# 4_cyber60-mxhs_power.net
KiCad netlist of a schematic drawn in Altium Designer
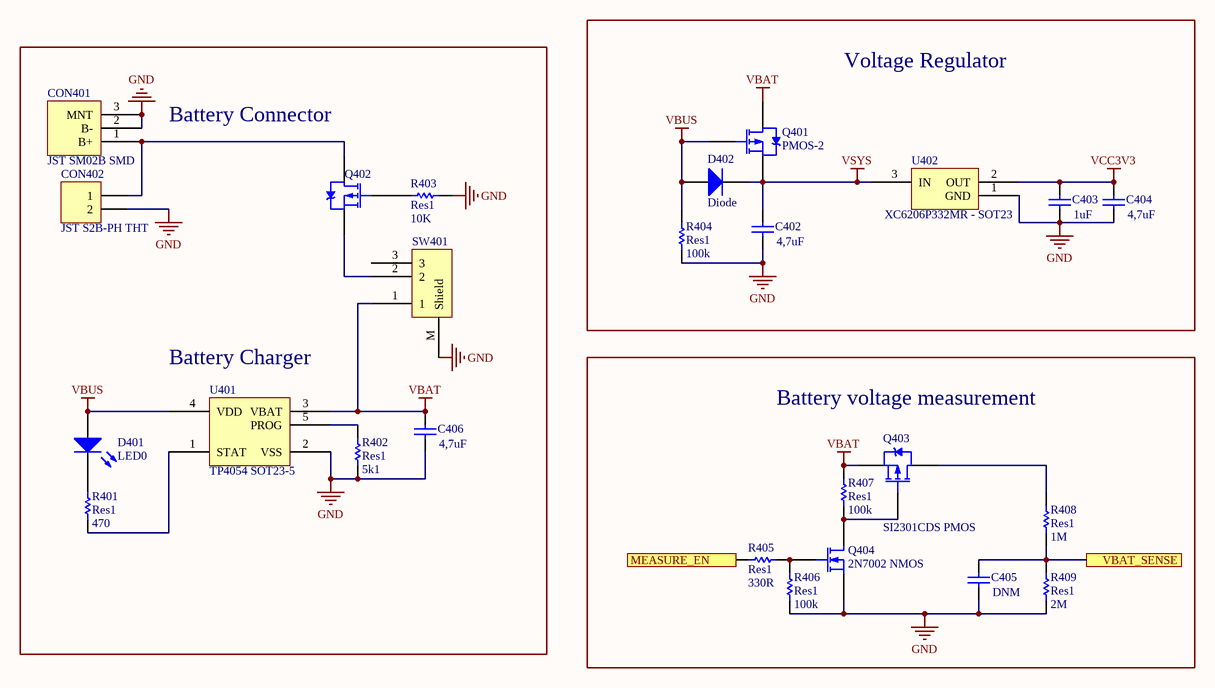
[diagram p0: 4_cyber60-mxhs_power.SchDoc]

(export (version "E")
  (design (tool "Eeschema 10.0.6"))
  (components
    (comp (ref "C402")
      (value "4,7uF")
      (footprint "C0603[1608]")
      (description "Capacitor")
      (fields (field (name "LCSC PART #") "C19666") (field (name "MRF.PART") "CL10A475KO8NNNC"))
      (libsource (lib "Miscellaneous Devices") (part "Cap"))
    )
    (comp (ref "C403")
      (value "1uF")
      (footprint "C0603[1608]")
      (description "Capacitor")
      (fields (field (name "MFG") "KEMET") (field (name "LCSC PART #") "C15849"))
      (libsource (lib "Miscellaneous Devices") (part "Cap"))
    )
    (comp (ref "C404")
      (value "4,7uF")
      (footprint "C0603[1608]")
      (description "Capacitor")
      (fields (field (name "LCSC PART #") "C19666") (field (name "MRF.PART") "CL10A475KO8NNNC"))
      (libsource (lib "Miscellaneous Devices") (part "Cap"))
    )
    (comp (ref "C405")
      (value "DNM")
      (footprint "C0603[1608]")
      (description "Capacitor")
      (libsource (lib "Miscellaneous Devices") (part "Cap"))
    )
    (comp (ref "C406")
      (value "4,7uF")
      (footprint "C0603[1608]")
      (description "Capacitor")
      (fields (field (name "LCSC PART #") "C19666") (field (name "MRF.PART") "CL10A475KO8NNNC"))
      (libsource (lib "Miscellaneous Devices") (part "Cap"))
    )
    (comp (ref "CON401")
      (value "JST SM02B SMD")
      (footprint "JST SM02B-SRSS-TB")
      (fields (field (name "LCSC PART #") "C160402") (field (name "MRF.PART") "SM02B-SRSS-TB(LF)(SN)"))
      (libsource (lib "Keebs") (part "JST S2B-PH-SM4-TB"))
    )
    (comp (ref "CON402")
      (value "JST S2B-PH THT")
      (footprint "Keebs:JST S2B-PH-K(LF)(SN)")
      (description "Header, 2-Pin")
      (fields (field (name "LCSC PART #") "C265016") (field (name "MRF.PART") "S2B-PH-K(LF)(SN)"))
      (libsource (lib "Miscellaneous Connectors") (part "Header 2"))
    )
    (comp (ref "D401")
      (value "LED0")
      (footprint "LED0603[1608]")
      (description "Typical INFRARED GaAs LED")
      (fields (field (name "LCSC PART #") "C72038") (field (name "MRF.PART") "19-213/Y2C-CQ2R2L/3T(CY)"))
      (libsource (lib "Miscellaneous Devices") (part "LED0"))
    )
    (comp (ref "D402")
      (value "Diode")
      (footprint "SOD-123")
      (description "Default Diode")
      (fields (field (name "LCSC PART #") "C8598") (field (name "MRF.PART") "B5819W"))
      (libsource (lib "Miscellaneous Devices") (part "Diode"))
    )
    (comp (ref "Q401")
      (value "PMOS-2")
      (footprint "SOT-23-3")
      (description "P-Channel Power MOSFET")
      (fields (field (name "MRF.PART") "SI2301CDS-T1-GE3") (field (name "LCSC PART #") "C10487"))
      (libsource (lib "Miscellaneous Devices") (part "PMOS-2"))
    )
    (comp (ref "Q402")
      (value "PMOS-2")
      (footprint "SOT-23-3")
      (description "P-Channel Power MOSFET")
      (fields (field (name "LCSC PART #") "C10487") (field (name "MRF.PART") "SI2301CDS-T1-GE3"))
      (libsource (lib "Miscellaneous Devices") (part "PMOS-2"))
    )
    (comp (ref "Q403")
      (value "SI2301CDS PMOS")
      (footprint "SOT-23-3")
      (description "P-Channel Power MOSFET")
      (fields (field (name "MRF.PART") "SI2301CDS-T1-GE3") (field (name "LCSC PART #") "C10487"))
      (libsource (lib "Miscellaneous Devices") (part "PMOS-2"))
    )
    (comp (ref "Q404")
      (value "2N7002 NMOS")
      (footprint "SOT-23-3")
      (description "N-Channel MOSFET")
      (fields (field (name "LCSC PART #") "C8545") (field (name "MRF.PART") "2N7002"))
      (libsource (lib "Miscellaneous Devices") (part "MOSFET-N"))
    )
    (comp (ref "R401")
      (value "Res1")
      (footprint "R0603[1608]")
      (description "Resistor")
      (fields
        (field (name "ALTIUM_VALUE") "470")
        (field (name "MFG") "Panasonic Electronic Components")
        (field (name "LCSC PART #") "C23179")
      )
      (libsource (lib "Miscellaneous Devices") (part "Res1"))
    )
    (comp (ref "R402")
      (value "Res1")
      (footprint "R0603[1608]")
      (description "Resistor")
      (fields
        (field (name "ALTIUM_VALUE") "5k1")
        (field (name "MFG") "Panasonic Electronic Components")
        (field (name "LCSC PART #") "C23186")
      )
      (libsource (lib "Miscellaneous Devices") (part "Res1"))
    )
    (comp (ref "R403")
      (value "Res1")
      (footprint "R0603[1608]")
      (description "Resistor")
      (fields
        (field (name "ALTIUM_VALUE") "10K")
        (field (name "MFG") "Panasonic Electronic Components")
        (field (name "LCSC PART #") "C25804")
      )
      (libsource (lib "Miscellaneous Devices") (part "Res1"))
    )
    (comp (ref "R404")
      (value "Res1")
      (footprint "R0603[1608]")
      (description "Resistor")
      (fields
        (field (name "ALTIUM_VALUE") "100k")
        (field (name "MRF.PART") "0603WAF1003T5E")
        (field (name "LCSC PART #") "C25803")
      )
      (libsource (lib "Miscellaneous Devices") (part "Res1"))
    )
    (comp (ref "R405")
      (value "Res1")
      (footprint "R0603[1608]")
      (description "Resistor")
      (fields
        (field (name "ALTIUM_VALUE") "330R")
        (field (name "LCSC PART #") "C23138")
        (field (name "MRF.PART") "0603WAF3300T5E")
      )
      (libsource (lib "Miscellaneous Devices") (part "Res1"))
    )
    (comp (ref "R406")
      (value "Res1")
      (footprint "R0603[1608]")
      (description "Resistor")
      (fields
        (field (name "ALTIUM_VALUE") "100k")
        (field (name "MRF.PART") "0603WAF1003T5E")
        (field (name "LCSC PART #") "C25803")
      )
      (libsource (lib "Miscellaneous Devices") (part "Res1"))
    )
    (comp (ref "R407")
      (value "Res1")
      (footprint "R0603[1608]")
      (description "Resistor")
      (fields
        (field (name "ALTIUM_VALUE") "100k")
        (field (name "MRF.PART") "0603WAF1003T5E")
        (field (name "LCSC PART #") "C25803")
      )
      (libsource (lib "Miscellaneous Devices") (part "Res1"))
    )
    (comp (ref "R408")
      (value "Res1")
      (footprint "R0603[1608]")
      (description "Resistor")
      (fields
        (field (name "ALTIUM_VALUE") "1M")
        (field (name "MRF.PART") "0603WAF1004T5E")
        (field (name "LCSC PART #") "C22935")
      )
      (libsource (lib "Miscellaneous Devices") (part "Res1"))
    )
    (comp (ref "R409")
      (value "Res1")
      (footprint "R0603[1608]")
      (description "Resistor")
      (fields
        (field (name "ALTIUM_VALUE") "2M")
        (field (name "MRF.PART") "0603WAF2004T5E")
        (field (name "LCSC PART #") "C22976")
      )
      (libsource (lib "Miscellaneous Devices") (part "Res1"))
    )
    (comp (ref "SW401")
      (value "Korean Hroparts Elec K3-1296S-E2")
      (footprint "Korean Hroparts Elec K3-1296S-E2")
      (fields (field (name "LCSC PART #") "C136659"))
      (libsource (lib "Keebs") (part "Korean Hroparts Elec K3-1296S-E2"))
    )
    (comp (ref "U401")
      (value "TP4054 SOT23-5")
      (footprint "SOT-23-5")
      (fields (field (name "LCSC PART #") "C32574") (field (name "MRF.PART") "TP4054"))
      (libsource (lib "Keebs") (part "MCP73831"))
    )
    (comp (ref "U402")
      (value "XC6206P332MR - SOT23")
      (footprint "SOT-23-3")
      (fields
        (field (name "LCSC PART #") "C5446")
        (field (name "MRF.PART") "XC6206P332MR")
        (field (name "MFG") "Texas Instruments")
      )
      (libsource (lib "Keebs") (part "SOT23 LDO"))
    )
  )
  (nets
    (net (code "1") (name "/MEASURE_EN") (class "Default")
      (node (ref "R405") (pin "1") (pinfunction "1_1") (pintype "passive"))
    )
    (net (code "2") (name "/VBAT_SENSE") (class "Default")
      (node (ref "C405") (pin "2") (pinfunction "2_2") (pintype "passive"))
      (node (ref "R408") (pin "2") (pinfunction "2_2") (pintype "passive"))
      (node (ref "R409") (pin "1") (pinfunction "1_1") (pintype "passive"))
    )
    (net (code "3") (name "GND") (class "Default")
      (node (ref "C402") (pin "1") (pinfunction "1_1") (pintype "passive"))
      (node (ref "C403") (pin "1") (pinfunction "1_1") (pintype "passive"))
      (node (ref "C404") (pin "1") (pinfunction "1_1") (pintype "passive"))
      (node (ref "C405") (pin "1") (pinfunction "1_1") (pintype "passive"))
      (node (ref "C406") (pin "1") (pinfunction "1_1") (pintype "passive"))
      (node (ref "CON401") (pin "2") (pinfunction "B-_2") (pintype "passive"))
      (node (ref "CON401") (pin "3") (pinfunction "MNT_3") (pintype "passive"))
      (node (ref "CON402") (pin "2") (pinfunction "2_2") (pintype "passive"))
      (node (ref "Q404") (pin "2") (pinfunction "S_2") (pintype "passive"))
      (node (ref "R402") (pin "2") (pinfunction "2_2") (pintype "passive"))
      (node (ref "R403") (pin "2") (pinfunction "2_2") (pintype "passive"))
      (node (ref "R404") (pin "2") (pinfunction "2_2") (pintype "passive"))
      (node (ref "R406") (pin "2") (pinfunction "2_2") (pintype "passive"))
      (node (ref "R409") (pin "2") (pinfunction "2_2") (pintype "passive"))
      (node (ref "SW401") (pin "M") (pinfunction "Shield_M") (pintype "passive"))
      (node (ref "U401") (pin "2") (pinfunction "VSS_2") (pintype "passive"))
      (node (ref "U402") (pin "1") (pinfunction "GND_1") (pintype "passive"))
    )
    (net (code "4") (name "Net-(CON401-B+)") (class "Default")
      (node (ref "CON401") (pin "1") (pinfunction "B+_1") (pintype "passive"))
      (node (ref "CON402") (pin "1") (pinfunction "1_1") (pintype "passive"))
      (node (ref "Q402") (pin "3") (pinfunction "D_3") (pintype "passive"))
    )
    (net (code "5") (name "Net-(D401-K)") (class "Default")
      (node (ref "D401") (pin "2") (pinfunction "K_2") (pintype "passive"))
      (node (ref "R401") (pin "2") (pinfunction "2_2") (pintype "passive"))
    )
    (net (code "6") (name "Net-(Q402-G)") (class "Default")
      (node (ref "Q402") (pin "1") (pinfunction "G_1") (pintype "passive"))
      (node (ref "R403") (pin "1") (pinfunction "1_1") (pintype "passive"))
    )
    (net (code "7") (name "Net-(Q402-S)") (class "Default")
      (node (ref "Q402") (pin "2") (pinfunction "S_2") (pintype "passive"))
      (node (ref "SW401") (pin "2") (pinfunction "2_2") (pintype "passive"))
    )
    (net (code "8") (name "Net-(Q403-D)") (class "Default")
      (node (ref "Q403") (pin "3") (pinfunction "D_3") (pintype "passive"))
      (node (ref "R408") (pin "1") (pinfunction "1_1") (pintype "passive"))
    )
    (net (code "9") (name "Net-(Q403-G)") (class "Default")
      (node (ref "Q403") (pin "1") (pinfunction "G_1") (pintype "passive"))
      (node (ref "Q404") (pin "3") (pinfunction "D_3") (pintype "passive"))
      (node (ref "R407") (pin "2") (pinfunction "2_2") (pintype "passive"))
    )
    (net (code "10") (name "Net-(Q404-G)") (class "Default")
      (node (ref "Q404") (pin "1") (pinfunction "G_1") (pintype "passive"))
      (node (ref "R405") (pin "2") (pinfunction "2_2") (pintype "passive"))
      (node (ref "R406") (pin "1") (pinfunction "1_1") (pintype "passive"))
    )
    (net (code "11") (name "Net-(U401-PROG)") (class "Default")
      (node (ref "R402") (pin "1") (pinfunction "1_1") (pintype "passive"))
      (node (ref "U401") (pin "5") (pinfunction "PROG_5") (pintype "passive"))
    )
    (net (code "12") (name "Net-(U401-STAT)") (class "Default")
      (node (ref "R401") (pin "1") (pinfunction "1_1") (pintype "passive"))
      (node (ref "U401") (pin "1") (pinfunction "STAT_1") (pintype "passive"))
    )
    (net (code "13") (name "VBAT") (class "Default")
      (node (ref "C406") (pin "2") (pinfunction "2_2") (pintype "passive"))
      (node (ref "Q401") (pin "3") (pinfunction "D_3") (pintype "passive"))
      (node (ref "Q403") (pin "2") (pinfunction "S_2") (pintype "passive"))
      (node (ref "R407") (pin "1") (pinfunction "1_1") (pintype "passive"))
      (node (ref "SW401") (pin "1") (pinfunction "1_1") (pintype "passive"))
      (node (ref "U401") (pin "3") (pinfunction "VBAT_3") (pintype "passive"))
    )
    (net (code "14") (name "VBUS") (class "Default")
      (node (ref "D401") (pin "1") (pinfunction "A_1") (pintype "passive"))
      (node (ref "D402") (pin "1") (pinfunction "A_1") (pintype "passive"))
      (node (ref "Q401") (pin "1") (pinfunction "G_1") (pintype "passive"))
      (node (ref "R404") (pin "1") (pinfunction "1_1") (pintype "passive"))
      (node (ref "U401") (pin "4") (pinfunction "VDD_4") (pintype "passive"))
    )
    (net (code "15") (name "VCC3V3") (class "Default")
      (node (ref "C403") (pin "2") (pinfunction "2_2") (pintype "passive"))
      (node (ref "C404") (pin "2") (pinfunction "2_2") (pintype "passive"))
      (node (ref "U402") (pin "2") (pinfunction "OUT_2") (pintype "passive"))
    )
    (net (code "16") (name "VSYS") (class "Default")
      (node (ref "C402") (pin "2") (pinfunction "2_2") (pintype "passive"))
      (node (ref "D402") (pin "2") (pinfunction "K_2") (pintype "passive"))
      (node (ref "Q401") (pin "2") (pinfunction "S_2") (pintype "passive"))
      (node (ref "U402") (pin "3") (pinfunction "IN_3") (pintype "passive"))
    )
    (net (code "17") (name "unconnected-(SW401-Pad3)") (class "Default")
      (node (ref "SW401") (pin "3") (pinfunction "3_3") (pintype "passive"))
    )
  )
)
